# MCU.net
KiCad netlist of a schematic drawn in Altium Designer
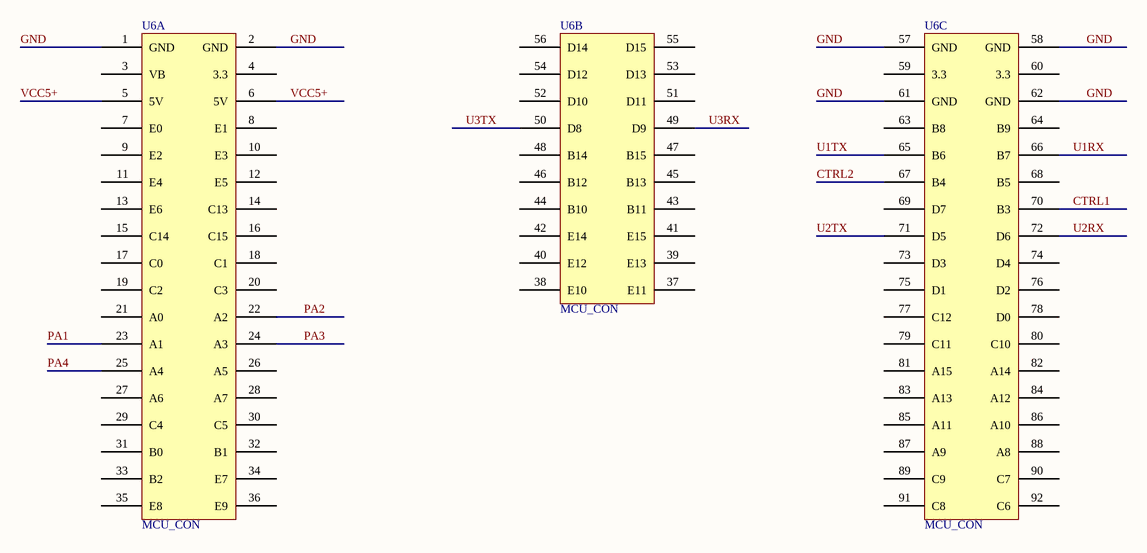
[diagram p0: MCU.SchDoc]

(export (version "E")
  (design (tool "Eeschema 10.0.6"))
  (components
    (comp (ref "U6") (value "MCU_CON") (footprint "MCU_CON") (libsource (lib "Schlib1") (part "MCU_CON")))
  )
  (nets
    (net (code "1") (name "/CTRL1") (class "Default")
      (node (ref "U6") (pin "70") (pinfunction "B3_70") (pintype "passive"))
    )
    (net (code "2") (name "/CTRL2") (class "Default")
      (node (ref "U6") (pin "67") (pinfunction "B4_67") (pintype "passive"))
    )
    (net (code "3") (name "/GND") (class "Default")
      (node (ref "U6") (pin "1") (pinfunction "GND_1") (pintype "passive"))
      (node (ref "U6") (pin "2") (pinfunction "GND_2") (pintype "passive"))
      (node (ref "U6") (pin "57") (pinfunction "GND_57") (pintype "passive"))
      (node (ref "U6") (pin "58") (pinfunction "GND_58") (pintype "passive"))
      (node (ref "U6") (pin "61") (pinfunction "GND_61") (pintype "passive"))
      (node (ref "U6") (pin "62") (pinfunction "GND_62") (pintype "passive"))
    )
    (net (code "4") (name "/PA1") (class "Default")
      (node (ref "U6") (pin "23") (pinfunction "A1_23") (pintype "passive"))
    )
    (net (code "5") (name "/PA2") (class "Default")
      (node (ref "U6") (pin "22") (pinfunction "A2_22") (pintype "passive"))
    )
    (net (code "6") (name "/PA3") (class "Default")
      (node (ref "U6") (pin "24") (pinfunction "A3_24") (pintype "passive"))
    )
    (net (code "7") (name "/PA4") (class "Default")
      (node (ref "U6") (pin "25") (pinfunction "A4_25") (pintype "passive"))
    )
    (net (code "8") (name "/U1RX") (class "Default")
      (node (ref "U6") (pin "66") (pinfunction "B7_66") (pintype "passive"))
    )
    (net (code "9") (name "/U1TX") (class "Default")
      (node (ref "U6") (pin "65") (pinfunction "B6_65") (pintype "passive"))
    )
    (net (code "10") (name "/U2RX") (class "Default")
      (node (ref "U6") (pin "72") (pinfunction "D6_72") (pintype "passive"))
    )
    (net (code "11") (name "/U2TX") (class "Default")
      (node (ref "U6") (pin "71") (pinfunction "D5_71") (pintype "passive"))
    )
    (net (code "12") (name "/U3RX") (class "Default")
      (node (ref "U6") (pin "49") (pinfunction "D9_49") (pintype "passive"))
    )
    (net (code "13") (name "/U3TX") (class "Default")
      (node (ref "U6") (pin "50") (pinfunction "D8_50") (pintype "passive"))
    )
    (net (code "14") (name "/VCC5+") (class "Default")
      (node (ref "U6") (pin "5") (pinfunction "5V_5") (pintype "passive"))
      (node (ref "U6") (pin "6") (pinfunction "5V_6") (pintype "passive"))
    )
    (net (code "15") (name "unconnected-(U6A-3.3-Pad4)") (class "Default")
      (node (ref "U6") (pin "4") (pinfunction "3.3_4") (pintype "passive"))
    )
    (net (code "16") (name "unconnected-(U6A-A0-Pad21)") (class "Default")
      (node (ref "U6") (pin "21") (pinfunction "A0_21") (pintype "passive"))
    )
    (net (code "17") (name "unconnected-(U6A-A5-Pad26)") (class "Default")
      (node (ref "U6") (pin "26") (pinfunction "A5_26") (pintype "passive"))
    )
    (net (code "18") (name "unconnected-(U6A-A6-Pad27)") (class "Default")
      (node (ref "U6") (pin "27") (pinfunction "A6_27") (pintype "passive"))
    )
    (net (code "19") (name "unconnected-(U6A-A7-Pad28)") (class "Default")
      (node (ref "U6") (pin "28") (pinfunction "A7_28") (pintype "passive"))
    )
    (net (code "20") (name "unconnected-(U6A-B0-Pad31)") (class "Default")
      (node (ref "U6") (pin "31") (pinfunction "B0_31") (pintype "passive"))
    )
    (net (code "21") (name "unconnected-(U6A-B1-Pad32)") (class "Default")
      (node (ref "U6") (pin "32") (pinfunction "B1_32") (pintype "passive"))
    )
    (net (code "22") (name "unconnected-(U6A-B2-Pad33)") (class "Default")
      (node (ref "U6") (pin "33") (pinfunction "B2_33") (pintype "passive"))
    )
    (net (code "23") (name "unconnected-(U6A-C0-Pad17)") (class "Default")
      (node (ref "U6") (pin "17") (pinfunction "C0_17") (pintype "passive"))
    )
    (net (code "24") (name "unconnected-(U6A-C1-Pad18)") (class "Default")
      (node (ref "U6") (pin "18") (pinfunction "C1_18") (pintype "passive"))
    )
    (net (code "25") (name "unconnected-(U6A-C2-Pad19)") (class "Default")
      (node (ref "U6") (pin "19") (pinfunction "C2_19") (pintype "passive"))
    )
    (net (code "26") (name "unconnected-(U6A-C3-Pad20)") (class "Default")
      (node (ref "U6") (pin "20") (pinfunction "C3_20") (pintype "passive"))
    )
    (net (code "27") (name "unconnected-(U6A-C4-Pad29)") (class "Default")
      (node (ref "U6") (pin "29") (pinfunction "C4_29") (pintype "passive"))
    )
    (net (code "28") (name "unconnected-(U6A-C5-Pad30)") (class "Default")
      (node (ref "U6") (pin "30") (pinfunction "C5_30") (pintype "passive"))
    )
    (net (code "29") (name "unconnected-(U6A-C13-Pad14)") (class "Default")
      (node (ref "U6") (pin "14") (pinfunction "C13_14") (pintype "passive"))
    )
    (net (code "30") (name "unconnected-(U6A-C14-Pad15)") (class "Default")
      (node (ref "U6") (pin "15") (pinfunction "C14_15") (pintype "passive"))
    )
    (net (code "31") (name "unconnected-(U6A-C15-Pad16)") (class "Default")
      (node (ref "U6") (pin "16") (pinfunction "C15_16") (pintype "passive"))
    )
    (net (code "32") (name "unconnected-(U6A-E0-Pad7)") (class "Default")
      (node (ref "U6") (pin "7") (pinfunction "E0_7") (pintype "passive"))
    )
    (net (code "33") (name "unconnected-(U6A-E1-Pad8)") (class "Default")
      (node (ref "U6") (pin "8") (pinfunction "E1_8") (pintype "passive"))
    )
    (net (code "34") (name "unconnected-(U6A-E2-Pad9)") (class "Default")
      (node (ref "U6") (pin "9") (pinfunction "E2_9") (pintype "passive"))
    )
    (net (code "35") (name "unconnected-(U6A-E3-Pad10)") (class "Default")
      (node (ref "U6") (pin "10") (pinfunction "E3_10") (pintype "passive"))
    )
    (net (code "36") (name "unconnected-(U6A-E4-Pad11)") (class "Default")
      (node (ref "U6") (pin "11") (pinfunction "E4_11") (pintype "passive"))
    )
    (net (code "37") (name "unconnected-(U6A-E5-Pad12)") (class "Default")
      (node (ref "U6") (pin "12") (pinfunction "E5_12") (pintype "passive"))
    )
    (net (code "38") (name "unconnected-(U6A-E6-Pad13)") (class "Default")
      (node (ref "U6") (pin "13") (pinfunction "E6_13") (pintype "passive"))
    )
    (net (code "39") (name "unconnected-(U6A-E7-Pad34)") (class "Default")
      (node (ref "U6") (pin "34") (pinfunction "E7_34") (pintype "passive"))
    )
    (net (code "40") (name "unconnected-(U6A-E8-Pad35)") (class "Default")
      (node (ref "U6") (pin "35") (pinfunction "E8_35") (pintype "passive"))
    )
    (net (code "41") (name "unconnected-(U6A-E9-Pad36)") (class "Default")
      (node (ref "U6") (pin "36") (pinfunction "E9_36") (pintype "passive"))
    )
    (net (code "42") (name "unconnected-(U6A-VB-Pad3)") (class "Default")
      (node (ref "U6") (pin "3") (pinfunction "VB_3") (pintype "passive"))
    )
    (net (code "43") (name "unconnected-(U6B-B10-Pad44)") (class "Default")
      (node (ref "U6") (pin "44") (pinfunction "B10_44") (pintype "passive"))
    )
    (net (code "44") (name "unconnected-(U6B-B11-Pad43)") (class "Default")
      (node (ref "U6") (pin "43") (pinfunction "B11_43") (pintype "passive"))
    )
    (net (code "45") (name "unconnected-(U6B-B12-Pad46)") (class "Default")
      (node (ref "U6") (pin "46") (pinfunction "B12_46") (pintype "passive"))
    )
    (net (code "46") (name "unconnected-(U6B-B13-Pad45)") (class "Default")
      (node (ref "U6") (pin "45") (pinfunction "B13_45") (pintype "passive"))
    )
    (net (code "47") (name "unconnected-(U6B-B14-Pad48)") (class "Default")
      (node (ref "U6") (pin "48") (pinfunction "B14_48") (pintype "passive"))
    )
    (net (code "48") (name "unconnected-(U6B-B15-Pad47)") (class "Default")
      (node (ref "U6") (pin "47") (pinfunction "B15_47") (pintype "passive"))
    )
    (net (code "49") (name "unconnected-(U6B-D10-Pad52)") (class "Default")
      (node (ref "U6") (pin "52") (pinfunction "D10_52") (pintype "passive"))
    )
    (net (code "50") (name "unconnected-(U6B-D11-Pad51)") (class "Default")
      (node (ref "U6") (pin "51") (pinfunction "D11_51") (pintype "passive"))
    )
    (net (code "51") (name "unconnected-(U6B-D12-Pad54)") (class "Default")
      (node (ref "U6") (pin "54") (pinfunction "D12_54") (pintype "passive"))
    )
    (net (code "52") (name "unconnected-(U6B-D13-Pad53)") (class "Default")
      (node (ref "U6") (pin "53") (pinfunction "D13_53") (pintype "passive"))
    )
    (net (code "53") (name "unconnected-(U6B-D14-Pad56)") (class "Default")
      (node (ref "U6") (pin "56") (pinfunction "D14_56") (pintype "passive"))
    )
    (net (code "54") (name "unconnected-(U6B-D15-Pad55)") (class "Default")
      (node (ref "U6") (pin "55") (pinfunction "D15_55") (pintype "passive"))
    )
    (net (code "55") (name "unconnected-(U6B-E10-Pad38)") (class "Default")
      (node (ref "U6") (pin "38") (pinfunction "E10_38") (pintype "passive"))
    )
    (net (code "56") (name "unconnected-(U6B-E11-Pad37)") (class "Default")
      (node (ref "U6") (pin "37") (pinfunction "E11_37") (pintype "passive"))
    )
    (net (code "57") (name "unconnected-(U6B-E12-Pad40)") (class "Default")
      (node (ref "U6") (pin "40") (pinfunction "E12_40") (pintype "passive"))
    )
    (net (code "58") (name "unconnected-(U6B-E13-Pad39)") (class "Default")
      (node (ref "U6") (pin "39") (pinfunction "E13_39") (pintype "passive"))
    )
    (net (code "59") (name "unconnected-(U6B-E14-Pad42)") (class "Default")
      (node (ref "U6") (pin "42") (pinfunction "E14_42") (pintype "passive"))
    )
    (net (code "60") (name "unconnected-(U6B-E15-Pad41)") (class "Default")
      (node (ref "U6") (pin "41") (pinfunction "E15_41") (pintype "passive"))
    )
    (net (code "61") (name "unconnected-(U6C-3.3-Pad59)") (class "Default")
      (node (ref "U6") (pin "59") (pinfunction "3.3_59") (pintype "passive"))
    )
    (net (code "62") (name "unconnected-(U6C-3.3-Pad60)") (class "Default")
      (node (ref "U6") (pin "60") (pinfunction "3.3_60") (pintype "passive"))
    )
    (net (code "63") (name "unconnected-(U6C-A8-Pad88)") (class "Default")
      (node (ref "U6") (pin "88") (pinfunction "A8_88") (pintype "passive"))
    )
    (net (code "64") (name "unconnected-(U6C-A9-Pad87)") (class "Default")
      (node (ref "U6") (pin "87") (pinfunction "A9_87") (pintype "passive"))
    )
    (net (code "65") (name "unconnected-(U6C-A10-Pad86)") (class "Default")
      (node (ref "U6") (pin "86") (pinfunction "A10_86") (pintype "passive"))
    )
    (net (code "66") (name "unconnected-(U6C-A11-Pad85)") (class "Default")
      (node (ref "U6") (pin "85") (pinfunction "A11_85") (pintype "passive"))
    )
    (net (code "67") (name "unconnected-(U6C-A12-Pad84)") (class "Default")
      (node (ref "U6") (pin "84") (pinfunction "A12_84") (pintype "passive"))
    )
    (net (code "68") (name "unconnected-(U6C-A13-Pad83)") (class "Default")
      (node (ref "U6") (pin "83") (pinfunction "A13_83") (pintype "passive"))
    )
    (net (code "69") (name "unconnected-(U6C-A14-Pad82)") (class "Default")
      (node (ref "U6") (pin "82") (pinfunction "A14_82") (pintype "passive"))
    )
    (net (code "70") (name "unconnected-(U6C-A15-Pad81)") (class "Default")
      (node (ref "U6") (pin "81") (pinfunction "A15_81") (pintype "passive"))
    )
    (net (code "71") (name "unconnected-(U6C-B5-Pad68)") (class "Default")
      (node (ref "U6") (pin "68") (pinfunction "B5_68") (pintype "passive"))
    )
    (net (code "72") (name "unconnected-(U6C-B8-Pad63)") (class "Default")
      (node (ref "U6") (pin "63") (pinfunction "B8_63") (pintype "passive"))
    )
    (net (code "73") (name "unconnected-(U6C-B9-Pad64)") (class "Default")
      (node (ref "U6") (pin "64") (pinfunction "B9_64") (pintype "passive"))
    )
    (net (code "74") (name "unconnected-(U6C-C6-Pad92)") (class "Default")
      (node (ref "U6") (pin "92") (pinfunction "C6_92") (pintype "passive"))
    )
    (net (code "75") (name "unconnected-(U6C-C7-Pad90)") (class "Default")
      (node (ref "U6") (pin "90") (pinfunction "C7_90") (pintype "passive"))
    )
    (net (code "76") (name "unconnected-(U6C-C8-Pad91)") (class "Default")
      (node (ref "U6") (pin "91") (pinfunction "C8_91") (pintype "passive"))
    )
    (net (code "77") (name "unconnected-(U6C-C9-Pad89)") (class "Default")
      (node (ref "U6") (pin "89") (pinfunction "C9_89") (pintype "passive"))
    )
    (net (code "78") (name "unconnected-(U6C-C10-Pad80)") (class "Default")
      (node (ref "U6") (pin "80") (pinfunction "C10_80") (pintype "passive"))
    )
    (net (code "79") (name "unconnected-(U6C-C11-Pad79)") (class "Default")
      (node (ref "U6") (pin "79") (pinfunction "C11_79") (pintype "passive"))
    )
    (net (code "80") (name "unconnected-(U6C-C12-Pad77)") (class "Default")
      (node (ref "U6") (pin "77") (pinfunction "C12_77") (pintype "passive"))
    )
    (net (code "81") (name "unconnected-(U6C-D0-Pad78)") (class "Default")
      (node (ref "U6") (pin "78") (pinfunction "D0_78") (pintype "passive"))
    )
    (net (code "82") (name "unconnected-(U6C-D1-Pad75)") (class "Default")
      (node (ref "U6") (pin "75") (pinfunction "D1_75") (pintype "passive"))
    )
    (net (code "83") (name "unconnected-(U6C-D2-Pad76)") (class "Default")
      (node (ref "U6") (pin "76") (pinfunction "D2_76") (pintype "passive"))
    )
    (net (code "84") (name "unconnected-(U6C-D3-Pad73)") (class "Default")
      (node (ref "U6") (pin "73") (pinfunction "D3_73") (pintype "passive"))
    )
    (net (code "85") (name "unconnected-(U6C-D4-Pad74)") (class "Default")
      (node (ref "U6") (pin "74") (pinfunction "D4_74") (pintype "passive"))
    )
    (net (code "86") (name "unconnected-(U6C-D7-Pad69)") (class "Default")
      (node (ref "U6") (pin "69") (pinfunction "D7_69") (pintype "passive"))
    )
  )
)
